# Lowduino_Minimal.net
KiCad netlist of a schematic drawn in EAGLE
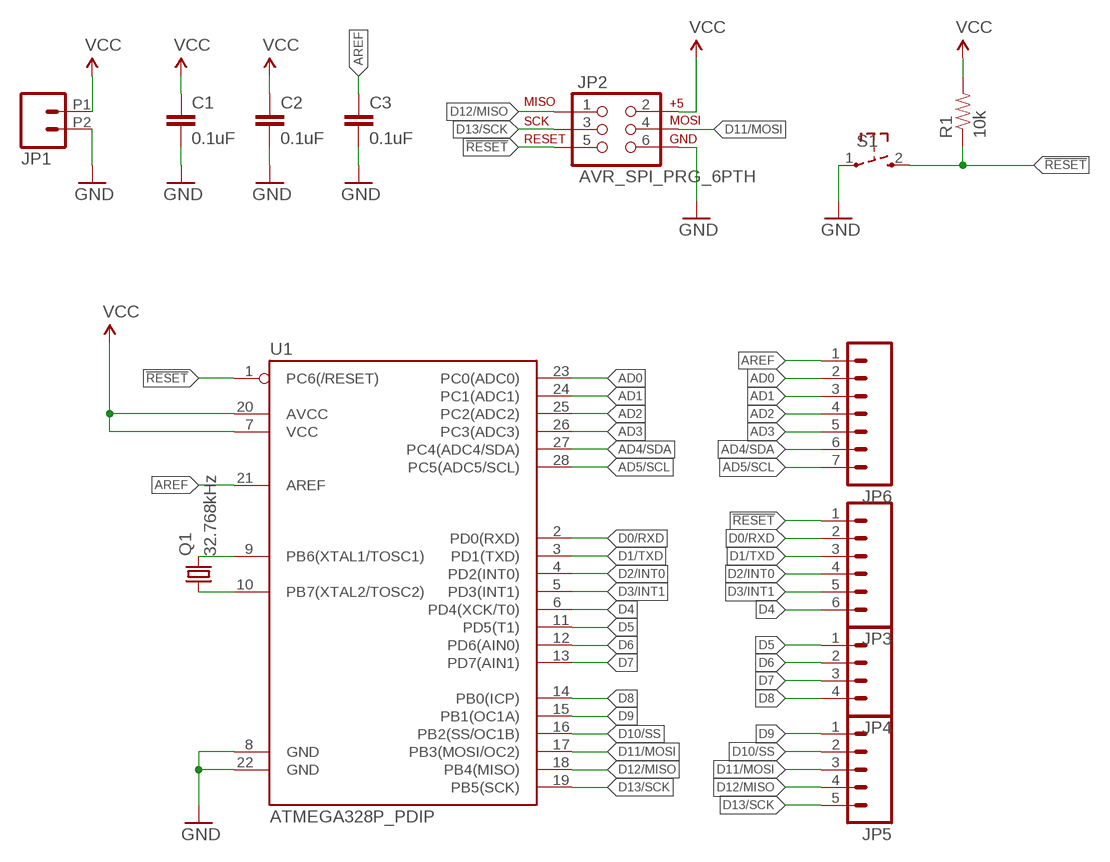
[diagram p0: schematic, sheet 1]

(export (version "E")
  (design (tool "Eeschema 10.0.6"))
  (components
    (comp (ref "C1")
      (value "0.1uF")
      (footprint "eagle-import:CAP-PTH-SMALL")
      (libsource (lib "eagle-import") (part "CAPPTH"))
    )
    (comp (ref "C2")
      (value "0.1uF")
      (footprint "eagle-import:CAP-PTH-SMALL")
      (libsource (lib "eagle-import") (part "CAPPTH"))
    )
    (comp (ref "C3")
      (value "0.1uF")
      (footprint "eagle-import:CAP-PTH-SMALL")
      (libsource (lib "eagle-import") (part "CAPPTH"))
    )
    (comp (ref "JP1")
      (value "M022.54MM_SCREWTERM")
      (footprint "eagle-import:1X02_2.54_SCREWTERM")
      (libsource (lib "eagle-import") (part "M022.54MM_SCREWTERM"))
    )
    (comp (ref "JP2")
      (value "AVR_SPI_PRG_6PTH")
      (footprint "eagle-import:2X3")
      (libsource (lib "eagle-import") (part "AVR_SPI_PRG_6PTH"))
    )
    (comp (ref "JP3")
      (value "M06LOCK")
      (footprint "eagle-import:1X06_LOCK")
      (libsource (lib "eagle-import") (part "M06LOCK"))
    )
    (comp (ref "JP4")
      (value "M04LOCK")
      (footprint "eagle-import:1X04_LOCK")
      (libsource (lib "eagle-import") (part "M04LOCK"))
    )
    (comp (ref "JP5")
      (value "M05LOCK")
      (footprint "eagle-import:1X05_LOCK")
      (libsource (lib "eagle-import") (part "M05LOCK"))
    )
    (comp (ref "JP6")
      (value "M07LOCK")
      (footprint "eagle-import:1X07_LOCK")
      (libsource (lib "eagle-import") (part "M07LOCK"))
    )
    (comp (ref "Q1")
      (value "32.768kHz")
      (footprint "eagle-import:TC26V")
      (libsource (lib "eagle-import") (part "CRYSTALTC26V"))
    )
    (comp (ref "R1")
      (value "10k")
      (footprint "eagle-import:AXIAL-0.1")
      (libsource (lib "eagle-import") (part "10KOHM-1/4W5%(PTH)VERT"))
    )
    (comp (ref "S1")
      (value "MJTP_6MM")
      (footprint "eagle-import:MJTP1243")
      (libsource (lib "eagle-import") (part "MJTP_6MM"))
    )
    (comp (ref "U1")
      (value "ATMEGA328P_PDIP")
      (footprint "eagle-import:DIL28-3")
      (libsource (lib "eagle-import") (part "ATMEGA328P_PDIP"))
    )
  )
  (nets
    (net (code "1") (name "/~{RESET}") (class "Default")
      (node (ref "JP2") (pin "5") (pinfunction "5_5") (pintype "passive"))
      (node (ref "JP3") (pin "1") (pinfunction "1_1") (pintype "passive"))
      (node (ref "R1") (pin "P$1") (pinfunction "1_P$1") (pintype "passive"))
      (node (ref "S1") (pin "2") (pinfunction "3_2") (pintype "passive"))
      (node (ref "U1") (pin "1") (pinfunction "PC6(/RESET)_1") (pintype "bidirectional"))
    )
    (net (code "2") (name "AD0") (class "Default")
      (node (ref "JP6") (pin "2") (pinfunction "2_2") (pintype "passive"))
      (node (ref "U1") (pin "23") (pinfunction "PC0(ADC0)_23") (pintype "bidirectional"))
    )
    (net (code "3") (name "AD1") (class "Default")
      (node (ref "JP6") (pin "3") (pinfunction "3_3") (pintype "passive"))
      (node (ref "U1") (pin "24") (pinfunction "PC1(ADC1)_24") (pintype "bidirectional"))
    )
    (net (code "4") (name "AD2") (class "Default")
      (node (ref "JP6") (pin "4") (pinfunction "4_4") (pintype "passive"))
      (node (ref "U1") (pin "25") (pinfunction "PC2(ADC2)_25") (pintype "bidirectional"))
    )
    (net (code "5") (name "AD3") (class "Default")
      (node (ref "JP6") (pin "5") (pinfunction "5_5") (pintype "passive"))
      (node (ref "U1") (pin "26") (pinfunction "PC3(ADC3)_26") (pintype "bidirectional"))
    )
    (net (code "6") (name "AD4{slash}SDA") (class "Default")
      (node (ref "JP6") (pin "6") (pinfunction "6_6") (pintype "passive"))
      (node (ref "U1") (pin "27") (pinfunction "PC4(ADC4/SDA)_27") (pintype "bidirectional"))
    )
    (net (code "7") (name "AD5{slash}SCL") (class "Default")
      (node (ref "JP6") (pin "7") (pinfunction "7_7") (pintype "passive"))
      (node (ref "U1") (pin "28") (pinfunction "PC5(ADC5/SCL)_28") (pintype "bidirectional"))
    )
    (net (code "8") (name "AREF") (class "Default")
      (node (ref "C3") (pin "1") (pinfunction "1_1") (pintype "passive"))
      (node (ref "JP6") (pin "1") (pinfunction "1_1") (pintype "passive"))
      (node (ref "U1") (pin "21") (pinfunction "AREF_21") (pintype "bidirectional"))
    )
    (net (code "9") (name "D0{slash}RXD") (class "Default")
      (node (ref "JP3") (pin "2") (pinfunction "2_2") (pintype "passive"))
      (node (ref "U1") (pin "2") (pinfunction "PD0(RXD)_2") (pintype "bidirectional"))
    )
    (net (code "10") (name "D1{slash}TXD") (class "Default")
      (node (ref "JP3") (pin "3") (pinfunction "3_3") (pintype "passive"))
      (node (ref "U1") (pin "3") (pinfunction "PD1(TXD)_3") (pintype "bidirectional"))
    )
    (net (code "11") (name "D2{slash}INT0") (class "Default")
      (node (ref "JP3") (pin "4") (pinfunction "4_4") (pintype "passive"))
      (node (ref "U1") (pin "4") (pinfunction "PD2(INT0)_4") (pintype "bidirectional"))
    )
    (net (code "12") (name "D3{slash}INT1") (class "Default")
      (node (ref "JP3") (pin "5") (pinfunction "5_5") (pintype "passive"))
      (node (ref "U1") (pin "5") (pinfunction "PD3(INT1)_5") (pintype "bidirectional"))
    )
    (net (code "13") (name "D4") (class "Default")
      (node (ref "JP3") (pin "6") (pinfunction "6_6") (pintype "passive"))
      (node (ref "U1") (pin "6") (pinfunction "PD4(XCK/T0)_6") (pintype "bidirectional"))
    )
    (net (code "14") (name "D5") (class "Default")
      (node (ref "JP4") (pin "1") (pinfunction "1_1") (pintype "passive"))
      (node (ref "U1") (pin "11") (pinfunction "PD5(T1)_11") (pintype "bidirectional"))
    )
    (net (code "15") (name "D6") (class "Default")
      (node (ref "JP4") (pin "2") (pinfunction "2_2") (pintype "passive"))
      (node (ref "U1") (pin "12") (pinfunction "PD6(AIN0)_12") (pintype "bidirectional"))
    )
    (net (code "16") (name "D7") (class "Default")
      (node (ref "JP4") (pin "3") (pinfunction "3_3") (pintype "passive"))
      (node (ref "U1") (pin "13") (pinfunction "PD7(AIN1)_13") (pintype "bidirectional"))
    )
    (net (code "17") (name "D8") (class "Default")
      (node (ref "JP4") (pin "4") (pinfunction "4_4") (pintype "passive"))
      (node (ref "U1") (pin "14") (pinfunction "PB0(ICP)_14") (pintype "bidirectional"))
    )
    (net (code "18") (name "D9") (class "Default")
      (node (ref "JP5") (pin "1") (pinfunction "1_1") (pintype "passive"))
      (node (ref "U1") (pin "15") (pinfunction "PB1(OC1A)_15") (pintype "bidirectional"))
    )
    (net (code "19") (name "D10{slash}SS") (class "Default")
      (node (ref "JP5") (pin "2") (pinfunction "2_2") (pintype "passive"))
      (node (ref "U1") (pin "16") (pinfunction "PB2(SS/OC1B)_16") (pintype "bidirectional"))
    )
    (net (code "20") (name "D11{slash}MOSI") (class "Default")
      (node (ref "JP2") (pin "4") (pinfunction "4_4") (pintype "passive"))
      (node (ref "JP5") (pin "3") (pinfunction "3_3") (pintype "passive"))
      (node (ref "U1") (pin "17") (pinfunction "PB3(MOSI/OC2)_17") (pintype "bidirectional"))
    )
    (net (code "21") (name "D12{slash}MISO") (class "Default")
      (node (ref "JP2") (pin "1") (pinfunction "1_1") (pintype "passive"))
      (node (ref "JP5") (pin "4") (pinfunction "4_4") (pintype "passive"))
      (node (ref "U1") (pin "18") (pinfunction "PB4(MISO)_18") (pintype "bidirectional"))
    )
    (net (code "22") (name "D13{slash}SCK") (class "Default")
      (node (ref "JP2") (pin "3") (pinfunction "3_3") (pintype "passive"))
      (node (ref "JP5") (pin "5") (pinfunction "5_5") (pintype "passive"))
      (node (ref "U1") (pin "19") (pinfunction "PB5(SCK)_19") (pintype "bidirectional"))
    )
    (net (code "23") (name "GND") (class "Default")
      (node (ref "C1") (pin "2") (pinfunction "2_2") (pintype "passive"))
      (node (ref "C2") (pin "2") (pinfunction "2_2") (pintype "passive"))
      (node (ref "C3") (pin "2") (pinfunction "2_2") (pintype "passive"))
      (node (ref "JP1") (pin "P2") (pinfunction "2_P2") (pintype "passive"))
      (node (ref "JP2") (pin "6") (pinfunction "6_6") (pintype "passive"))
      (node (ref "S1") (pin "1") (pinfunction "1_1") (pintype "passive"))
      (node (ref "U1") (pin "22") (pinfunction "GND_22") (pintype "bidirectional"))
      (node (ref "U1") (pin "8") (pinfunction "GND_8") (pintype "bidirectional"))
    )
    (net (code "24") (name "Net-(U1-PB6(XTAL1{slash}TOSC1))") (class "Default")
      (node (ref "Q1") (pin "2") (pinfunction "2_2") (pintype "passive"))
      (node (ref "U1") (pin "9") (pinfunction "PB6(XTAL1/TOSC1)_9") (pintype "bidirectional"))
    )
    (net (code "25") (name "Net-(U1-PB7(XTAL2{slash}TOSC2))") (class "Default")
      (node (ref "Q1") (pin "1") (pinfunction "1_1") (pintype "passive"))
      (node (ref "U1") (pin "10") (pinfunction "PB7(XTAL2/TOSC2)_10") (pintype "bidirectional"))
    )
    (net (code "26") (name "VCC") (class "Default")
      (node (ref "C1") (pin "1") (pinfunction "1_1") (pintype "passive"))
      (node (ref "C2") (pin "1") (pinfunction "1_1") (pintype "passive"))
      (node (ref "JP1") (pin "P1") (pinfunction "1_P1") (pintype "passive"))
      (node (ref "JP2") (pin "2") (pinfunction "2_2") (pintype "passive"))
      (node (ref "R1") (pin "P$2") (pinfunction "2_P$2") (pintype "passive"))
      (node (ref "U1") (pin "20") (pinfunction "AVCC_20") (pintype "bidirectional"))
      (node (ref "U1") (pin "7") (pinfunction "VCC_7") (pintype "bidirectional"))
    )
  )
)
